# StereoAmplifier-BA5412.net
KiCad netlist of a schematic drawn in EAGLE
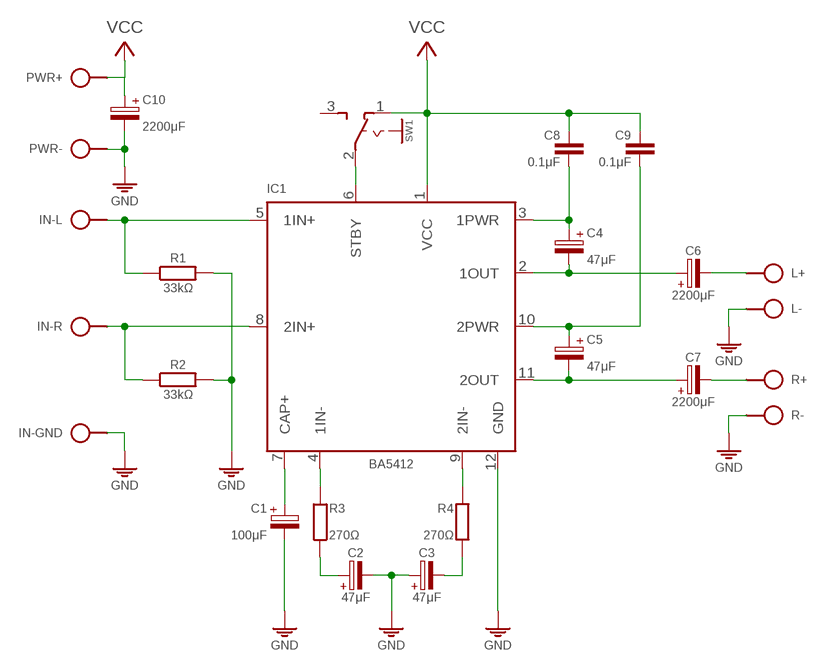
[diagram p0: schematic, sheet 1]

(export (version "E")
  (design (tool "Eeschema 10.0.6"))
  (components
    (comp (ref "C1")
      (value "100μF")
      (footprint "eagle-import:E2.5-4_V")
      (libsource (lib "eagle-import") (part "CPOLE2,5-4/V"))
    )
    (comp (ref "C2")
      (value "47μF")
      (footprint "eagle-import:E2.5-4_V")
      (libsource (lib "eagle-import") (part "CPOLE2,5-4/V"))
    )
    (comp (ref "C3")
      (value "47μF")
      (footprint "eagle-import:E2.5-4_V")
      (libsource (lib "eagle-import") (part "CPOLE2,5-4/V"))
    )
    (comp (ref "C4")
      (value "47μF")
      (footprint "eagle-import:E2.5-4_V")
      (libsource (lib "eagle-import") (part "CPOLE2,5-4/V"))
    )
    (comp (ref "C5")
      (value "47μF")
      (footprint "eagle-import:E2.5-4_V")
      (libsource (lib "eagle-import") (part "CPOLE2,5-4/V"))
    )
    (comp (ref "C6")
      (value "2200μF")
      (footprint "eagle-import:E5-6")
      (libsource (lib "eagle-import") (part "CPOLE5-6"))
    )
    (comp (ref "C7")
      (value "2200μF")
      (footprint "eagle-import:E5-6")
      (libsource (lib "eagle-import") (part "CPOLE5-6"))
    )
    (comp (ref "C8")
      (value "0.1μF")
      (footprint "eagle-import:C050-020X044")
      (libsource (lib "eagle-import") (part "C050-020X044"))
    )
    (comp (ref "C9")
      (value "0.1μF")
      (footprint "eagle-import:C050-020X044")
      (libsource (lib "eagle-import") (part "C050-020X044"))
    )
    (comp (ref "C10")
      (value "2200μF")
      (footprint "eagle-import:E5-6")
      (libsource (lib "eagle-import") (part "CPOLE5-6"))
    )
    (comp (ref "IC1")
      (value "BA5412")
      (footprint "eagle-import:SIL12")
      (libsource (lib "eagle-import") (part "BA5412"))
    )
    (comp (ref "IN")
      (value "SAUDIO")
      (footprint "eagle-import:SPAD-3")
      (libsource (lib "eagle-import") (part "SAUDIO"))
    )
    (comp (ref "L")
      (value "SPAD+-")
      (footprint "eagle-import:SPAD+-")
      (libsource (lib "eagle-import") (part "SPAD+-"))
    )
    (comp (ref "PWR")
      (value "SPAD+-")
      (footprint "eagle-import:SPAD+-")
      (libsource (lib "eagle-import") (part "SPAD+-"))
    )
    (comp (ref "R")
      (value "SPAD+-")
      (footprint "eagle-import:SPAD+-")
      (libsource (lib "eagle-import") (part "SPAD+-"))
    )
    (comp (ref "R1")
      (value "33kΩ")
      (footprint "eagle-import:0204_10")
      (libsource (lib "eagle-import") (part "R-H0204/10"))
    )
    (comp (ref "R2")
      (value "33kΩ")
      (footprint "eagle-import:0204_10")
      (libsource (lib "eagle-import") (part "R-H0204/10"))
    )
    (comp (ref "R3")
      (value "270Ω")
      (footprint "eagle-import:0204_10")
      (libsource (lib "eagle-import") (part "R0204/10"))
    )
    (comp (ref "R4")
      (value "270Ω")
      (footprint "eagle-import:0204_10")
      (libsource (lib "eagle-import") (part "R0204/10"))
    )
    (comp (ref "SW1")
      (value "SL-SW-1P-2T-H")
      (footprint "eagle-import:SLSW-1P2T-H")
      (libsource (lib "eagle-import") (part "SL-SW-1P-2T-H"))
    )
  )
  (nets
    (net (code "1") (name "GND") (class "Default")
      (node (ref "C1") (pin "-") (pinfunction "-_-") (pintype "passive"))
      (node (ref "C10") (pin "-") (pinfunction "-_-") (pintype "passive"))
      (node (ref "C2") (pin "-") (pinfunction "-_-") (pintype "passive"))
      (node (ref "C3") (pin "+") (pinfunction "+_+") (pintype "passive"))
      (node (ref "IC1") (pin "12") (pinfunction "GND_12") (pintype "bidirectional"))
      (node (ref "IN") (pin "2") (pinfunction "P$1_2") (pintype "passive"))
      (node (ref "L") (pin "1") (pinfunction "P$1_1") (pintype "passive"))
      (node (ref "PWR") (pin "1") (pinfunction "P$1_1") (pintype "passive"))
      (node (ref "R") (pin "1") (pinfunction "P$1_1") (pintype "passive"))
      (node (ref "R1") (pin "2") (pinfunction "2_2") (pintype "passive"))
      (node (ref "R2") (pin "2") (pinfunction "2_2") (pintype "passive"))
    )
    (net (code "2") (name "Net-(C2-Pad+)") (class "Default")
      (node (ref "C2") (pin "+") (pinfunction "+_+") (pintype "passive"))
      (node (ref "R3") (pin "1") (pinfunction "1_1") (pintype "passive"))
    )
    (net (code "3") (name "Net-(C3-Pad-)") (class "Default")
      (node (ref "C3") (pin "-") (pinfunction "-_-") (pintype "passive"))
      (node (ref "R4") (pin "1") (pinfunction "1_1") (pintype "passive"))
    )
    (net (code "4") (name "Net-(IC1-1IN+)") (class "Default")
      (node (ref "IC1") (pin "5") (pinfunction "1IN+_5") (pintype "bidirectional"))
      (node (ref "IN") (pin "1") (pinfunction "P$1_1") (pintype "passive"))
      (node (ref "R1") (pin "1") (pinfunction "1_1") (pintype "passive"))
    )
    (net (code "5") (name "Net-(IC1-1IN-)") (class "Default")
      (node (ref "IC1") (pin "4") (pinfunction "1IN-_4") (pintype "bidirectional"))
      (node (ref "R3") (pin "2") (pinfunction "2_2") (pintype "passive"))
    )
    (net (code "6") (name "Net-(IC1-1OUT)") (class "Default")
      (node (ref "C4") (pin "-") (pinfunction "-_-") (pintype "passive"))
      (node (ref "C6") (pin "+") (pinfunction "+_+") (pintype "passive"))
      (node (ref "IC1") (pin "2") (pinfunction "1OUT_2") (pintype "bidirectional"))
    )
    (net (code "7") (name "Net-(IC1-1PWR)") (class "Default")
      (node (ref "C4") (pin "+") (pinfunction "+_+") (pintype "passive"))
      (node (ref "C8") (pin "2") (pinfunction "2_2") (pintype "passive"))
      (node (ref "IC1") (pin "3") (pinfunction "1PWR_3") (pintype "bidirectional"))
    )
    (net (code "8") (name "Net-(IC1-2IN+)") (class "Default")
      (node (ref "IC1") (pin "8") (pinfunction "2IN+_8") (pintype "bidirectional"))
      (node (ref "IN") (pin "3") (pinfunction "P$1_3") (pintype "passive"))
      (node (ref "R2") (pin "1") (pinfunction "1_1") (pintype "passive"))
    )
    (net (code "9") (name "Net-(IC1-2IN-)") (class "Default")
      (node (ref "IC1") (pin "9") (pinfunction "2IN-_9") (pintype "bidirectional"))
      (node (ref "R4") (pin "2") (pinfunction "2_2") (pintype "passive"))
    )
    (net (code "10") (name "Net-(IC1-2OUT)") (class "Default")
      (node (ref "C5") (pin "-") (pinfunction "-_-") (pintype "passive"))
      (node (ref "C7") (pin "+") (pinfunction "+_+") (pintype "passive"))
      (node (ref "IC1") (pin "11") (pinfunction "2OUT_11") (pintype "bidirectional"))
    )
    (net (code "11") (name "Net-(IC1-2PWR)") (class "Default")
      (node (ref "C5") (pin "+") (pinfunction "+_+") (pintype "passive"))
      (node (ref "C9") (pin "2") (pinfunction "2_2") (pintype "passive"))
      (node (ref "IC1") (pin "10") (pinfunction "2PWR_10") (pintype "bidirectional"))
    )
    (net (code "12") (name "Net-(IC1-CAP+)") (class "Default")
      (node (ref "C1") (pin "+") (pinfunction "+_+") (pintype "passive"))
      (node (ref "IC1") (pin "7") (pinfunction "CAP+_7") (pintype "bidirectional"))
    )
    (net (code "13") (name "Net-(IC1-STBY)") (class "Default")
      (node (ref "IC1") (pin "6") (pinfunction "STBY_6") (pintype "bidirectional"))
      (node (ref "SW1") (pin "2") (pinfunction "P_2") (pintype "passive"))
    )
    (net (code "14") (name "Net-(LA-P$1)") (class "Default")
      (node (ref "C6") (pin "-") (pinfunction "-_-") (pintype "passive"))
      (node (ref "L") (pin "2") (pinfunction "P$1_2") (pintype "passive"))
    )
    (net (code "15") (name "Net-(RA-P$1)") (class "Default")
      (node (ref "C7") (pin "-") (pinfunction "-_-") (pintype "passive"))
      (node (ref "R") (pin "2") (pinfunction "P$1_2") (pintype "passive"))
    )
    (net (code "16") (name "VCC") (class "Default")
      (node (ref "C10") (pin "+") (pinfunction "+_+") (pintype "passive"))
      (node (ref "C8") (pin "1") (pinfunction "1_1") (pintype "passive"))
      (node (ref "C9") (pin "1") (pinfunction "1_1") (pintype "passive"))
      (node (ref "IC1") (pin "1") (pinfunction "VCC_1") (pintype "bidirectional"))
      (node (ref "PWR") (pin "2") (pinfunction "P$1_2") (pintype "passive"))
      (node (ref "SW1") (pin "1") (pinfunction "O_1") (pintype "passive"))
    )
    (net (code "17") (name "unconnected-(SW1-S-Pad3)") (class "Default")
      (node (ref "SW1") (pin "3") (pinfunction "S_3") (pintype "passive"))
    )
  )
)
